# chaprintesting.net
KiCad netlist of a schematic drawn in EAGLE
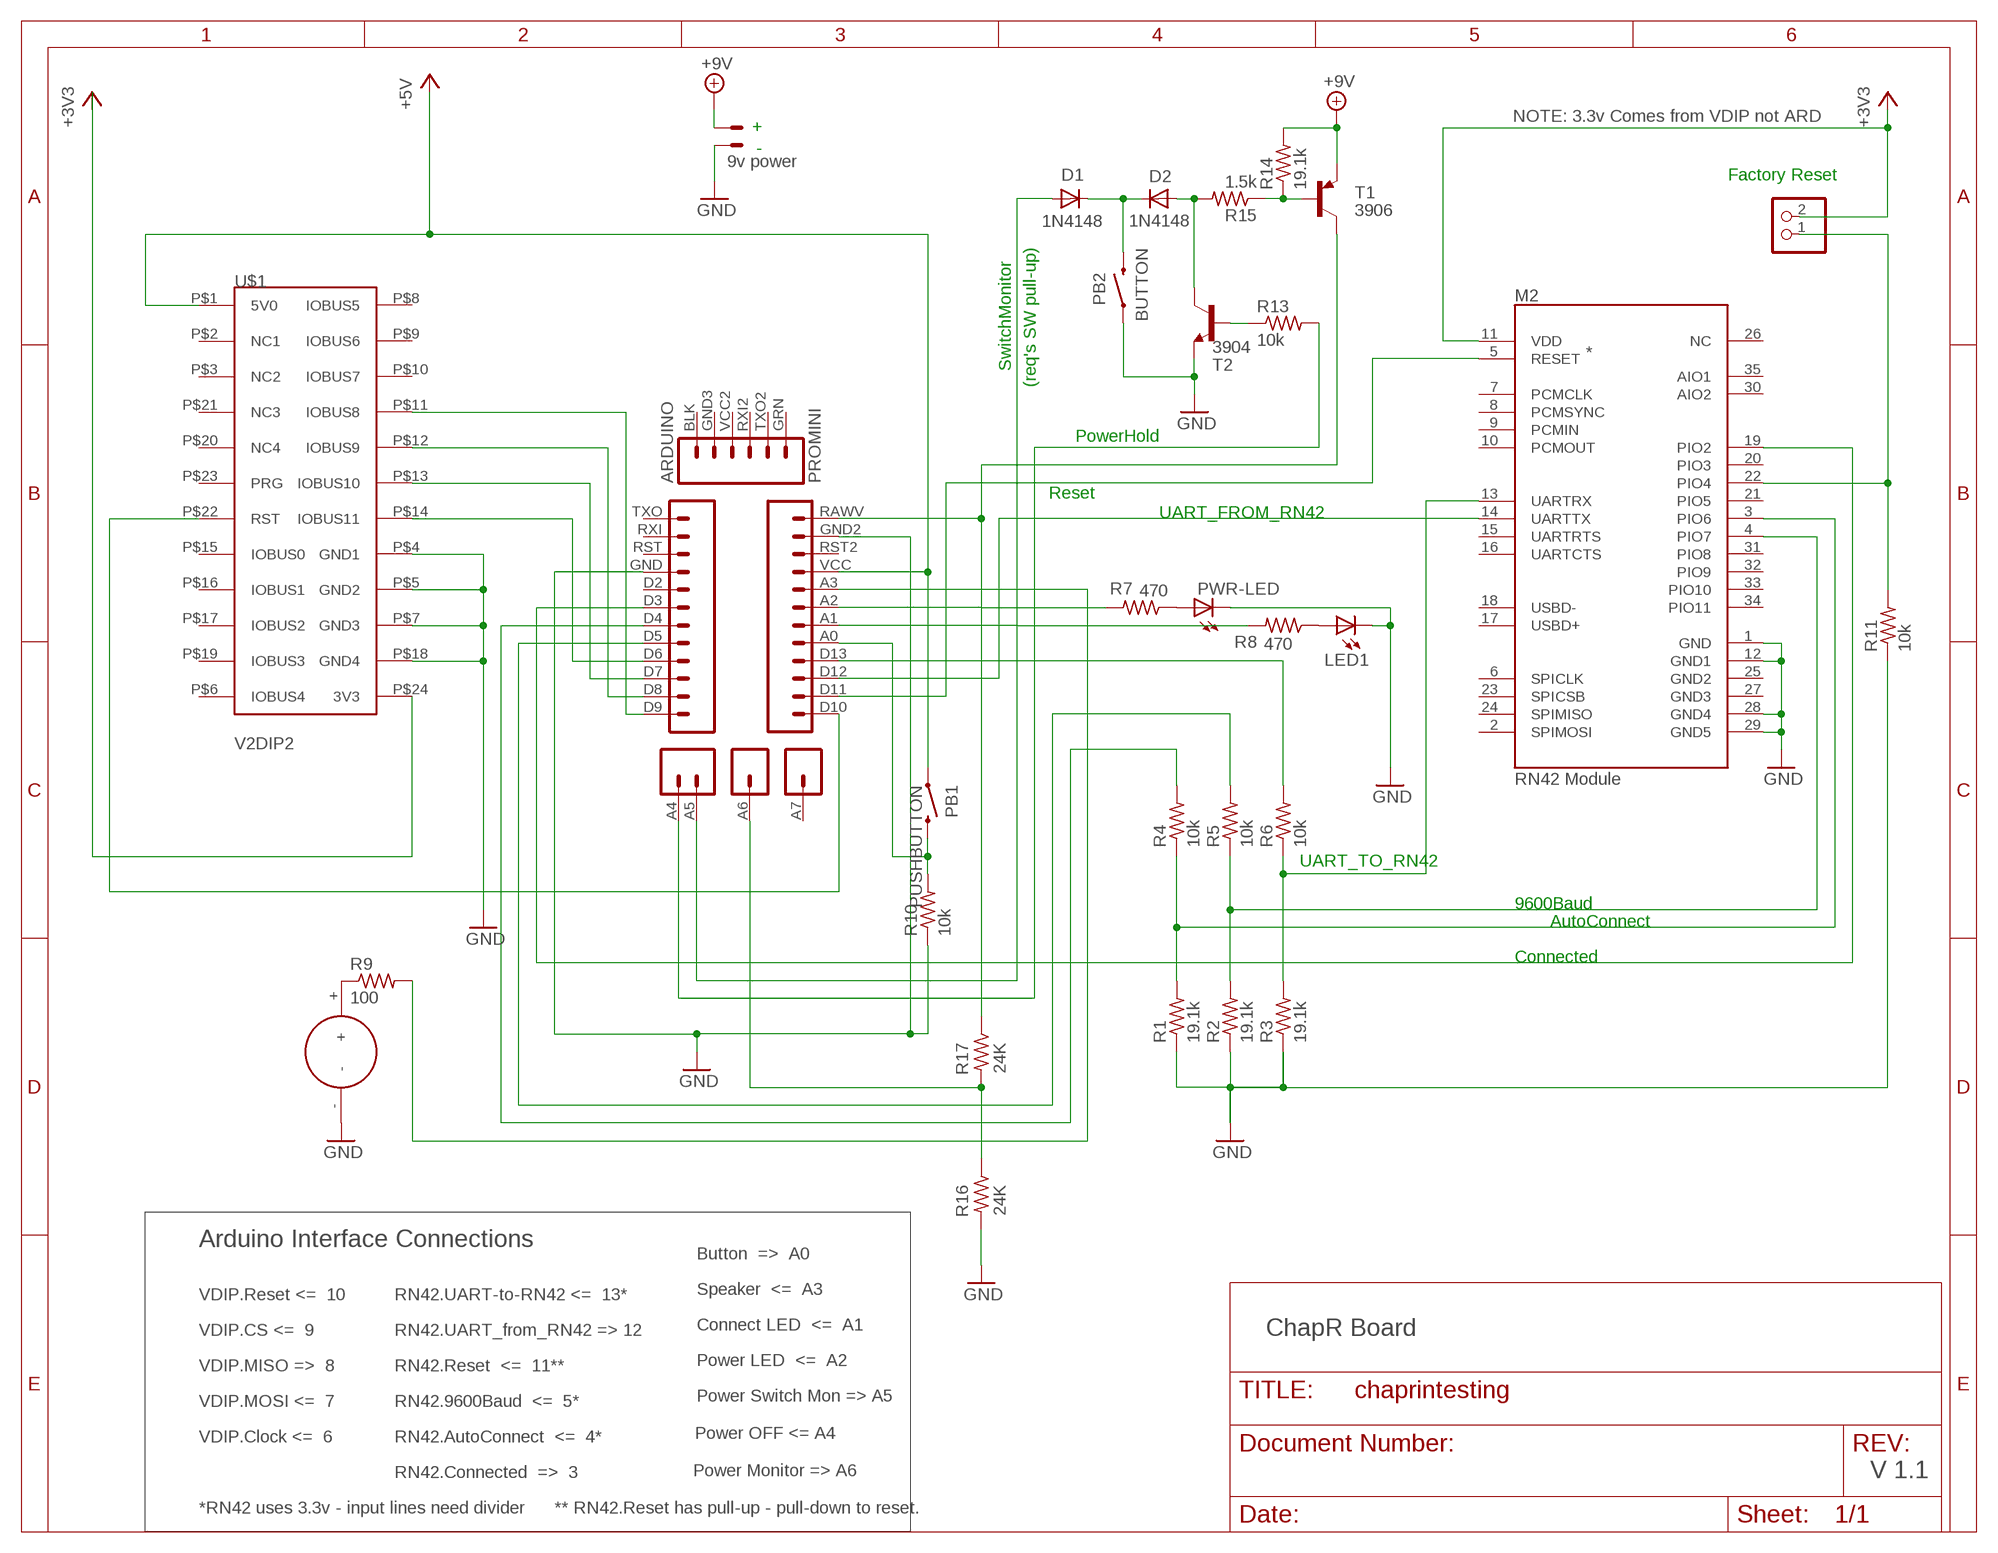
[diagram p0: schematic, sheet 1]

(export (version "E")
  (design (tool "Eeschema 10.0.6"))
  (components
    (comp (ref "-")
      (value "9v power")
      (footprint "eagle-import:22-23-2021")
      (fields (field (name "MF") "MOLEX") (field (name "MPN") "22-23-2021"))
      (libsource (lib "eagle-import") (part "22-23-2021"))
    )
    (comp (ref "ARDUINO")
      (value "PROMINI")
      (footprint "eagle-import:PROMINI")
      (libsource (lib "eagle-import") (part "PROMINI"))
    )
    (comp (ref "D1")
      (value "1N4148")
      (footprint "eagle-import:DO35-7")
      (libsource (lib "eagle-import") (part "1N4148DO35-7"))
    )
    (comp (ref "D2")
      (value "1N4148")
      (footprint "eagle-import:DO35-7")
      (libsource (lib "eagle-import") (part "1N4148DO35-7"))
    )
    (comp (ref "JP1")
      (value "PINHD-1X2")
      (footprint "eagle-import:1X02")
      (libsource (lib "eagle-import") (part "PINHD-1X2"))
    )
    (comp (ref "LED1")
      (value "LED3MM")
      (footprint "eagle-import:LED3MM")
      (libsource (lib "eagle-import") (part "LED3MM"))
    )
    (comp (ref "M2")
      (value "RN42 Module")
      (footprint "eagle-import:RN41")
      (libsource (lib "eagle-import") (part "BLUETOOTH-RN41{dblquote}"))
    )
    (comp (ref "PB1")
      (value "PUSHBUTTON")
      (footprint "eagle-import:2-PIN-PUSHBUTTON")
      (libsource (lib "eagle-import") (part "PUSHBUTTON"))
    )
    (comp (ref "PB2")
      (value "BUTTON")
      (footprint "eagle-import:2-PIN-PUSHBUTTON")
      (libsource (lib "eagle-import") (part "PUSHBUTTON"))
    )
    (comp (ref "PWR-LED")
      (value "LED3MM")
      (footprint "eagle-import:LED3MM")
      (libsource (lib "eagle-import") (part "LED3MM"))
    )
    (comp (ref "R1")
      (value "19.1k")
      (footprint "eagle-import:0207_10")
      (libsource (lib "eagle-import") (part "R-US_0207/10"))
    )
    (comp (ref "R2")
      (value "19.1k")
      (footprint "eagle-import:0207_10")
      (libsource (lib "eagle-import") (part "R-US_0207/10"))
    )
    (comp (ref "R3")
      (value "19.1k")
      (footprint "eagle-import:0207_10")
      (libsource (lib "eagle-import") (part "R-US_0207/10"))
    )
    (comp (ref "R4")
      (value "10k")
      (footprint "eagle-import:0207_10")
      (libsource (lib "eagle-import") (part "R-US_0207/10"))
    )
    (comp (ref "R5")
      (value "10k")
      (footprint "eagle-import:0207_10")
      (libsource (lib "eagle-import") (part "R-US_0207/10"))
    )
    (comp (ref "R6")
      (value "10k")
      (footprint "eagle-import:0207_10")
      (libsource (lib "eagle-import") (part "R-US_0207/10"))
    )
    (comp (ref "R7")
      (value "470")
      (footprint "eagle-import:0207_10")
      (libsource (lib "eagle-import") (part "R-US_0207/10"))
    )
    (comp (ref "R8")
      (value "470")
      (footprint "eagle-import:0207_10")
      (libsource (lib "eagle-import") (part "R-US_0207/10"))
    )
    (comp (ref "R9")
      (value "100")
      (footprint "eagle-import:0207_10")
      (libsource (lib "eagle-import") (part "R-US_0207/10"))
    )
    (comp (ref "R10")
      (value "10k")
      (footprint "eagle-import:0207_10")
      (libsource (lib "eagle-import") (part "R-US_0207/10"))
    )
    (comp (ref "R11")
      (value "10k")
      (footprint "eagle-import:0207_10")
      (libsource (lib "eagle-import") (part "R-US_0207/10"))
    )
    (comp (ref "R13")
      (value "10k")
      (footprint "eagle-import:0207_10")
      (libsource (lib "eagle-import") (part "R-US_0207/10"))
    )
    (comp (ref "R14")
      (value "19.1k")
      (footprint "eagle-import:0207_10")
      (libsource (lib "eagle-import") (part "R-US_0207/10"))
    )
    (comp (ref "R15")
      (value "1.5k")
      (footprint "eagle-import:0207_10")
      (libsource (lib "eagle-import") (part "R-US_0207/10"))
    )
    (comp (ref "R16")
      (value "24K")
      (footprint "eagle-import:0207_10")
      (libsource (lib "eagle-import") (part "R-US_0207/10"))
    )
    (comp (ref "R17")
      (value "24K")
      (footprint "eagle-import:0207_10")
      (libsource (lib "eagle-import") (part "R-US_0207/10"))
    )
    (comp (ref "T1")
      (value "3906")
      (footprint "eagle-import:TO92-EBC")
      (libsource (lib "eagle-import") (part "-PNP-TO92-EBC"))
    )
    (comp (ref "T2")
      (value "3904")
      (footprint "eagle-import:TO92-EBC")
      (libsource (lib "eagle-import") (part "-NPN-TO92-EBC"))
    )
    (comp (ref "U$1")
      (value "V2DIP2")
      (footprint "eagle-import:V2DIP2")
      (libsource (lib "eagle-import") (part "V2DIP2"))
    )
    (comp (ref "U$2")
      (value "SPEAKER")
      (footprint "eagle-import:SPEAKER")
      (libsource (lib "eagle-import") (part "SPEAKER"))
    )
  )
  (nets
    (net (code "1") (name "+3V3") (class "Default")
      (node (ref "JP1") (pin "2") (pinfunction "2_2") (pintype "passive"))
      (node (ref "M2") (pin "11") (pinfunction "VDD_11") (pintype "bidirectional"))
    )
    (net (code "2") (name "+5V") (class "Default")
      (node (ref "ARDUINO") (pin "VCC") (pinfunction "VCC_VCC") (pintype "passive"))
      (node (ref "PB1") (pin "P$1") (pinfunction "1_P$1") (pintype "passive"))
      (node (ref "U$1") (pin "P$1") (pinfunction "5V0_P$1") (pintype "bidirectional"))
    )
    (net (code "3") (name "+9V") (class "Default")
      (node (ref "-") (pin "2") (pinfunction "S_2") (pintype "passive"))
      (node (ref "R14") (pin "2") (pinfunction "2_2") (pintype "passive"))
      (node (ref "T1") (pin "E") (pinfunction "E_E") (pintype "passive"))
    )
    (net (code "4") (name "GND") (class "Default")
      (node (ref "-") (pin "1") (pinfunction "S_1") (pintype "passive"))
      (node (ref "ARDUINO") (pin "GND") (pinfunction "GND_GND") (pintype "passive"))
      (node (ref "ARDUINO") (pin "GND2") (pinfunction "GND2_GND2") (pintype "passive"))
      (node (ref "LED1") (pin "K") (pinfunction "C_K") (pintype "passive"))
      (node (ref "M2") (pin "1") (pinfunction "GND_1") (pintype "bidirectional"))
      (node (ref "M2") (pin "12") (pinfunction "GND1_12") (pintype "bidirectional"))
      (node (ref "M2") (pin "28") (pinfunction "GND4_28") (pintype "bidirectional"))
      (node (ref "M2") (pin "29") (pinfunction "GND5_29") (pintype "bidirectional"))
      (node (ref "PB2") (pin "P$1") (pinfunction "1_P$1") (pintype "passive"))
      (node (ref "PWR-LED") (pin "K") (pinfunction "C_K") (pintype "passive"))
      (node (ref "R1") (pin "1") (pinfunction "1_1") (pintype "passive"))
      (node (ref "R10") (pin "1") (pinfunction "1_1") (pintype "passive"))
      (node (ref "R11") (pin "1") (pinfunction "1_1") (pintype "passive"))
      (node (ref "R16") (pin "2") (pinfunction "2_2") (pintype "passive"))
      (node (ref "R2") (pin "1") (pinfunction "1_1") (pintype "passive"))
      (node (ref "R3") (pin "1") (pinfunction "1_1") (pintype "passive"))
      (node (ref "T2") (pin "E") (pinfunction "E_E") (pintype "passive"))
      (node (ref "U$1") (pin "P$18") (pinfunction "GND4_P$18") (pintype "bidirectional"))
      (node (ref "U$1") (pin "P$4") (pinfunction "GND1_P$4") (pintype "bidirectional"))
      (node (ref "U$1") (pin "P$5") (pinfunction "GND2_P$5") (pintype "bidirectional"))
      (node (ref "U$1") (pin "P$7") (pinfunction "GND3_P$7") (pintype "bidirectional"))
      (node (ref "U$2") (pin "-") (pinfunction "-_-") (pintype "bidirectional"))
    )
    (net (code "5") (name "Net-(ARDUINO-PadA1)") (class "Default")
      (node (ref "ARDUINO") (pin "A1") (pinfunction "A1_A1") (pintype "passive"))
      (node (ref "R8") (pin "2") (pinfunction "2_2") (pintype "passive"))
    )
    (net (code "6") (name "Net-(ARDUINO-PadA2)") (class "Default")
      (node (ref "ARDUINO") (pin "A2") (pinfunction "A2_A2") (pintype "passive"))
      (node (ref "R7") (pin "2") (pinfunction "2_2") (pintype "passive"))
    )
    (net (code "7") (name "Net-(ARDUINO-PadA3)") (class "Default")
      (node (ref "ARDUINO") (pin "A3") (pinfunction "A3_A3") (pintype "passive"))
      (node (ref "R9") (pin "2") (pinfunction "2_2") (pintype "passive"))
    )
    (net (code "8") (name "Net-(ARDUINO-PadA4)") (class "Default")
      (node (ref "ARDUINO") (pin "A4") (pinfunction "A4_A4") (pintype "passive"))
      (node (ref "R13") (pin "2") (pinfunction "2_2") (pintype "passive"))
    )
    (net (code "9") (name "Net-(ARDUINO-PadA5)") (class "Default")
      (node (ref "ARDUINO") (pin "A5") (pinfunction "A5_A5") (pintype "passive"))
      (node (ref "D1") (pin "A") (pinfunction "A_A") (pintype "passive"))
    )
    (net (code "10") (name "Net-(ARDUINO-PadA6)") (class "Default")
      (node (ref "ARDUINO") (pin "A6") (pinfunction "A6_A6") (pintype "passive"))
      (node (ref "R16") (pin "1") (pinfunction "1_1") (pintype "passive"))
      (node (ref "R17") (pin "2") (pinfunction "2_2") (pintype "passive"))
    )
    (net (code "11") (name "Net-(ARDUINO-PadD4)") (class "Default")
      (node (ref "ARDUINO") (pin "D4") (pinfunction "D4_D4") (pintype "passive"))
      (node (ref "R4") (pin "2") (pinfunction "2_2") (pintype "passive"))
    )
    (net (code "12") (name "Net-(ARDUINO-PadD5)") (class "Default")
      (node (ref "ARDUINO") (pin "D5") (pinfunction "D5_D5") (pintype "passive"))
      (node (ref "R5") (pin "2") (pinfunction "2_2") (pintype "passive"))
    )
    (net (code "13") (name "Net-(ARDUINO-PadD13)") (class "Default")
      (node (ref "ARDUINO") (pin "D13") (pinfunction "D13_D13") (pintype "passive"))
      (node (ref "R6") (pin "2") (pinfunction "2_2") (pintype "passive"))
    )
    (net (code "14") (name "Net-(ARDUINO-PadRAWV)") (class "Default")
      (node (ref "ARDUINO") (pin "RAWV") (pinfunction "RAWV_RAWV") (pintype "passive"))
      (node (ref "R17") (pin "1") (pinfunction "1_1") (pintype "passive"))
      (node (ref "T1") (pin "C") (pinfunction "C_C") (pintype "passive"))
    )
    (net (code "15") (name "Net-(D2-PadA)") (class "Default")
      (node (ref "D2") (pin "A") (pinfunction "A_A") (pintype "passive"))
      (node (ref "R15") (pin "2") (pinfunction "2_2") (pintype "passive"))
      (node (ref "T2") (pin "C") (pinfunction "C_C") (pintype "passive"))
    )
    (net (code "16") (name "Net-(LED1-PadA)") (class "Default")
      (node (ref "LED1") (pin "A") (pinfunction "A_A") (pintype "passive"))
      (node (ref "R8") (pin "1") (pinfunction "1_1") (pintype "passive"))
    )
    (net (code "17") (name "Net-(M2-PIO2)") (class "Default")
      (node (ref "ARDUINO") (pin "D3") (pinfunction "D3_D3") (pintype "passive"))
      (node (ref "M2") (pin "19") (pinfunction "PIO2_19") (pintype "bidirectional"))
    )
    (net (code "18") (name "Net-(M2-PIO4)") (class "Default")
      (node (ref "JP1") (pin "1") (pinfunction "1_1") (pintype "passive"))
      (node (ref "M2") (pin "22") (pinfunction "PIO4_22") (pintype "bidirectional"))
      (node (ref "R11") (pin "2") (pinfunction "2_2") (pintype "passive"))
    )
    (net (code "19") (name "Net-(M2-PIO6)") (class "Default")
      (node (ref "M2") (pin "3") (pinfunction "PIO6_3") (pintype "bidirectional"))
      (node (ref "R1") (pin "2") (pinfunction "2_2") (pintype "passive"))
      (node (ref "R4") (pin "1") (pinfunction "1_1") (pintype "passive"))
    )
    (net (code "20") (name "Net-(M2-PIO7)") (class "Default")
      (node (ref "M2") (pin "4") (pinfunction "PIO7_4") (pintype "bidirectional"))
      (node (ref "R2") (pin "2") (pinfunction "2_2") (pintype "passive"))
      (node (ref "R5") (pin "1") (pinfunction "1_1") (pintype "passive"))
    )
    (net (code "21") (name "Net-(M2-RESET)") (class "Default")
      (node (ref "ARDUINO") (pin "D11") (pinfunction "D11_D11") (pintype "passive"))
      (node (ref "M2") (pin "5") (pinfunction "RESET_5") (pintype "bidirectional"))
    )
    (net (code "22") (name "Net-(M2-UARTRX)") (class "Default")
      (node (ref "M2") (pin "13") (pinfunction "UARTRX_13") (pintype "bidirectional"))
      (node (ref "R3") (pin "2") (pinfunction "2_2") (pintype "passive"))
      (node (ref "R6") (pin "1") (pinfunction "1_1") (pintype "passive"))
    )
    (net (code "23") (name "Net-(M2-UARTTX)") (class "Default")
      (node (ref "ARDUINO") (pin "D12") (pinfunction "D12_D12") (pintype "passive"))
      (node (ref "M2") (pin "14") (pinfunction "UARTTX_14") (pintype "bidirectional"))
    )
    (net (code "24") (name "Net-(PB1-2)") (class "Default")
      (node (ref "ARDUINO") (pin "A0") (pinfunction "A0_A0") (pintype "passive"))
      (node (ref "PB1") (pin "P$2") (pinfunction "2_P$2") (pintype "passive"))
      (node (ref "R10") (pin "2") (pinfunction "2_2") (pintype "passive"))
    )
    (net (code "25") (name "Net-(PB2-2)") (class "Default")
      (node (ref "D1") (pin "C") (pinfunction "C_C") (pintype "passive"))
      (node (ref "D2") (pin "C") (pinfunction "C_C") (pintype "passive"))
      (node (ref "PB2") (pin "P$2") (pinfunction "2_P$2") (pintype "passive"))
    )
    (net (code "26") (name "Net-(PWR-LED-PadA)") (class "Default")
      (node (ref "PWR-LED") (pin "A") (pinfunction "A_A") (pintype "passive"))
      (node (ref "R7") (pin "1") (pinfunction "1_1") (pintype "passive"))
    )
    (net (code "27") (name "Net-(R9-Pad1)") (class "Default")
      (node (ref "R9") (pin "1") (pinfunction "1_1") (pintype "passive"))
      (node (ref "U$2") (pin "+") (pinfunction "+_+") (pintype "bidirectional"))
    )
    (net (code "28") (name "Net-(R13-Pad1)") (class "Default")
      (node (ref "R13") (pin "1") (pinfunction "1_1") (pintype "passive"))
      (node (ref "T2") (pin "B") (pinfunction "B_B") (pintype "passive"))
    )
    (net (code "29") (name "Net-(R14-Pad1)") (class "Default")
      (node (ref "R14") (pin "1") (pinfunction "1_1") (pintype "passive"))
      (node (ref "R15") (pin "1") (pinfunction "1_1") (pintype "passive"))
      (node (ref "T1") (pin "B") (pinfunction "B_B") (pintype "passive"))
    )
    (net (code "30") (name "Net-(U$1-IOBUS8)") (class "Default")
      (node (ref "ARDUINO") (pin "D9") (pinfunction "D9_D9") (pintype "passive"))
      (node (ref "U$1") (pin "P$11") (pinfunction "IOBUS8_P$11") (pintype "bidirectional"))
    )
    (net (code "31") (name "Net-(U$1-IOBUS9)") (class "Default")
      (node (ref "ARDUINO") (pin "D8") (pinfunction "D8_D8") (pintype "passive"))
      (node (ref "U$1") (pin "P$12") (pinfunction "IOBUS9_P$12") (pintype "bidirectional"))
    )
    (net (code "32") (name "Net-(U$1-IOBUS10)") (class "Default")
      (node (ref "ARDUINO") (pin "D7") (pinfunction "D7_D7") (pintype "passive"))
      (node (ref "U$1") (pin "P$13") (pinfunction "IOBUS10_P$13") (pintype "bidirectional"))
    )
    (net (code "33") (name "Net-(U$1-IOBUS11)") (class "Default")
      (node (ref "ARDUINO") (pin "D6") (pinfunction "D6_D6") (pintype "passive"))
      (node (ref "U$1") (pin "P$14") (pinfunction "IOBUS11_P$14") (pintype "bidirectional"))
    )
    (net (code "34") (name "Net-(U$1-RST)") (class "Default")
      (node (ref "ARDUINO") (pin "D10") (pinfunction "D10_D10") (pintype "passive"))
      (node (ref "U$1") (pin "P$22") (pinfunction "RST_P$22") (pintype "bidirectional"))
    )
    (net (code "35") (name "unconnected-(ARDUINO-PadA7)") (class "Default")
      (node (ref "ARDUINO") (pin "A7") (pinfunction "A7_A7") (pintype "passive"))
    )
    (net (code "36") (name "unconnected-(ARDUINO-PadBLK)") (class "Default")
      (node (ref "ARDUINO") (pin "BLK") (pinfunction "BLK_BLK") (pintype "passive"))
    )
    (net (code "37") (name "unconnected-(ARDUINO-PadD2)") (class "Default")
      (node (ref "ARDUINO") (pin "D2") (pinfunction "D2_D2") (pintype "passive"))
    )
    (net (code "38") (name "unconnected-(ARDUINO-PadGND3)") (class "Default")
      (node (ref "ARDUINO") (pin "GND3") (pinfunction "GND3_GND3") (pintype "passive"))
    )
    (net (code "39") (name "unconnected-(ARDUINO-PadGRN)") (class "Default")
      (node (ref "ARDUINO") (pin "GRN") (pinfunction "GRN_GRN") (pintype "passive"))
    )
    (net (code "40") (name "unconnected-(ARDUINO-PadRST)") (class "Default")
      (node (ref "ARDUINO") (pin "RST") (pinfunction "RST_RST") (pintype "passive"))
    )
    (net (code "41") (name "unconnected-(ARDUINO-PadRST2)") (class "Default")
      (node (ref "ARDUINO") (pin "RST2") (pinfunction "RST2_RST2") (pintype "passive"))
    )
    (net (code "42") (name "unconnected-(ARDUINO-PadRXI)") (class "Default")
      (node (ref "ARDUINO") (pin "RXI") (pinfunction "RXI_RXI") (pintype "passive"))
    )
    (net (code "43") (name "unconnected-(ARDUINO-PadRXI2)") (class "Default")
      (node (ref "ARDUINO") (pin "RXI2") (pinfunction "RXI2_RXI2") (pintype "passive"))
    )
    (net (code "44") (name "unconnected-(ARDUINO-PadTXO)") (class "Default")
      (node (ref "ARDUINO") (pin "TXO") (pinfunction "TXO_TXO") (pintype "passive"))
    )
    (net (code "45") (name "unconnected-(ARDUINO-PadTXO2)") (class "Default")
      (node (ref "ARDUINO") (pin "TXO2") (pinfunction "TXO2_TXO2") (pintype "passive"))
    )
    (net (code "46") (name "unconnected-(ARDUINO-PadVCC2)") (class "Default")
      (node (ref "ARDUINO") (pin "VCC2") (pinfunction "VCC2_VCC2") (pintype "passive"))
    )
    (net (code "47") (name "unconnected-(M2-AIO1-Pad35)") (class "Default")
      (node (ref "M2") (pin "35") (pinfunction "AIO1_35") (pintype "bidirectional"))
    )
    (net (code "48") (name "unconnected-(M2-AIO2-Pad30)") (class "Default")
      (node (ref "M2") (pin "30") (pinfunction "AIO2_30") (pintype "bidirectional"))
    )
    (net (code "49") (name "unconnected-(M2-GND2-Pad25)") (class "Default")
      (node (ref "M2") (pin "25") (pinfunction "GND2_25") (pintype "bidirectional"))
    )
    (net (code "50") (name "unconnected-(M2-GND3-Pad27)") (class "Default")
      (node (ref "M2") (pin "27") (pinfunction "GND3_27") (pintype "bidirectional"))
    )
    (net (code "51") (name "unconnected-(M2-NC-Pad26)") (class "Default")
      (node (ref "M2") (pin "26") (pinfunction "NC_26") (pintype "bidirectional"))
    )
    (net (code "52") (name "unconnected-(M2-PCMCLK-Pad7)") (class "Default")
      (node (ref "M2") (pin "7") (pinfunction "PCMCLK_7") (pintype "bidirectional"))
    )
    (net (code "53") (name "unconnected-(M2-PCMIN-Pad9)") (class "Default")
      (node (ref "M2") (pin "9") (pinfunction "PCMIN_9") (pintype "bidirectional"))
    )
    (net (code "54") (name "unconnected-(M2-PCMOUT-Pad10)") (class "Default")
      (node (ref "M2") (pin "10") (pinfunction "PCMOUT_10") (pintype "bidirectional"))
    )
    (net (code "55") (name "unconnected-(M2-PCMSYNC-Pad8)") (class "Default")
      (node (ref "M2") (pin "8") (pinfunction "PCMSYNC_8") (pintype "bidirectional"))
    )
    (net (code "56") (name "unconnected-(M2-PIO3-Pad20)") (class "Default")
      (node (ref "M2") (pin "20") (pinfunction "PIO3_20") (pintype "bidirectional"))
    )
    (net (code "57") (name "unconnected-(M2-PIO5-Pad21)") (class "Default")
      (node (ref "M2") (pin "21") (pinfunction "PIO5_21") (pintype "bidirectional"))
    )
    (net (code "58") (name "unconnected-(M2-PIO8-Pad31)") (class "Default")
      (node (ref "M2") (pin "31") (pinfunction "PIO8_31") (pintype "bidirectional"))
    )
    (net (code "59") (name "unconnected-(M2-PIO9-Pad32)") (class "Default")
      (node (ref "M2") (pin "32") (pinfunction "PIO9_32") (pintype "bidirectional"))
    )
    (net (code "60") (name "unconnected-(M2-PIO10-Pad33)") (class "Default")
      (node (ref "M2") (pin "33") (pinfunction "PIO10_33") (pintype "bidirectional"))
    )
    (net (code "61") (name "unconnected-(M2-PIO11-Pad34)") (class "Default")
      (node (ref "M2") (pin "34") (pinfunction "PIO11_34") (pintype "bidirectional"))
    )
    (net (code "62") (name "unconnected-(M2-SPICLK-Pad6)") (class "Default")
      (node (ref "M2") (pin "6") (pinfunction "SPICLK_6") (pintype "bidirectional"))
    )
    (net (code "63") (name "unconnected-(M2-SPICSB-Pad23)") (class "Default")
      (node (ref "M2") (pin "23") (pinfunction "SPICSB_23") (pintype "bidirectional"))
    )
    (net (code "64") (name "unconnected-(M2-SPIMISO-Pad24)") (class "Default")
      (node (ref "M2") (pin "24") (pinfunction "SPIMISO_24") (pintype "bidirectional"))
    )
    (net (code "65") (name "unconnected-(M2-SPIMOSI-Pad2)") (class "Default")
      (node (ref "M2") (pin "2") (pinfunction "SPIMOSI_2") (pintype "bidirectional"))
    )
    (net (code "66") (name "unconnected-(M2-UARTCTS-Pad16)") (class "Default")
      (node (ref "M2") (pin "16") (pinfunction "UARTCTS_16") (pintype "bidirectional"))
    )
    (net (code "67") (name "unconnected-(M2-UARTRTS-Pad15)") (class "Default")
      (node (ref "M2") (pin "15") (pinfunction "UARTRTS_15") (pintype "bidirectional"))
    )
    (net (code "68") (name "unconnected-(M2-USBD+-Pad17)") (class "Default")
      (node (ref "M2") (pin "17") (pinfunction "USBD+_17") (pintype "bidirectional"))
    )
    (net (code "69") (name "unconnected-(M2-USBD--Pad18)") (class "Default")
      (node (ref "M2") (pin "18") (pinfunction "USBD-_18") (pintype "bidirectional"))
    )
    (net (code "70") (name "unconnected-(U$1-3V3-PadP$24)") (class "Default")
      (node (ref "U$1") (pin "P$24") (pinfunction "3V3_P$24") (pintype "bidirectional"))
    )
    (net (code "71") (name "unconnected-(U$1-IOBUS0-PadP$15)") (class "Default")
      (node (ref "U$1") (pin "P$15") (pinfunction "IOBUS0_P$15") (pintype "bidirectional"))
    )
    (net (code "72") (name "unconnected-(U$1-IOBUS1-PadP$16)") (class "Default")
      (node (ref "U$1") (pin "P$16") (pinfunction "IOBUS1_P$16") (pintype "bidirectional"))
    )
    (net (code "73") (name "unconnected-(U$1-IOBUS2-PadP$17)") (class "Default")
      (node (ref "U$1") (pin "P$17") (pinfunction "IOBUS2_P$17") (pintype "bidirectional"))
    )
    (net (code "74") (name "unconnected-(U$1-IOBUS3-PadP$19)") (class "Default")
      (node (ref "U$1") (pin "P$19") (pinfunction "IOBUS3_P$19") (pintype "bidirectional"))
    )
    (net (code "75") (name "unconnected-(U$1-IOBUS4-PadP$6)") (class "Default")
      (node (ref "U$1") (pin "P$6") (pinfunction "IOBUS4_P$6") (pintype "bidirectional"))
    )
    (net (code "76") (name "unconnected-(U$1-IOBUS5-PadP$8)") (class "Default")
      (node (ref "U$1") (pin "P$8") (pinfunction "IOBUS5_P$8") (pintype "bidirectional"))
    )
    (net (code "77") (name "unconnected-(U$1-IOBUS6-PadP$9)") (class "Default")
      (node (ref "U$1") (pin "P$9") (pinfunction "IOBUS6_P$9") (pintype "bidirectional"))
    )
    (net (code "78") (name "unconnected-(U$1-IOBUS7-PadP$10)") (class "Default")
      (node (ref "U$1") (pin "P$10") (pinfunction "IOBUS7_P$10") (pintype "bidirectional"))
    )
    (net (code "79") (name "unconnected-(U$1-NC1-PadP$2)") (class "Default")
      (node (ref "U$1") (pin "P$2") (pinfunction "NC1_P$2") (pintype "bidirectional"))
    )
    (net (code "80") (name "unconnected-(U$1-NC2-PadP$3)") (class "Default")
      (node (ref "U$1") (pin "P$3") (pinfunction "NC2_P$3") (pintype "bidirectional"))
    )
    (net (code "81") (name "unconnected-(U$1-NC3-PadP$21)") (class "Default")
      (node (ref "U$1") (pin "P$21") (pinfunction "NC3_P$21") (pintype "bidirectional"))
    )
    (net (code "82") (name "unconnected-(U$1-NC4-PadP$20)") (class "Default")
      (node (ref "U$1") (pin "P$20") (pinfunction "NC4_P$20") (pintype "bidirectional"))
    )
    (net (code "83") (name "unconnected-(U$1-PRG-PadP$23)") (class "Default")
      (node (ref "U$1") (pin "P$23") (pinfunction "PRG_P$23") (pintype "bidirectional"))
    )
  )
)
